# plug_in_A.net
KiCad netlist of a schematic drawn in EAGLE
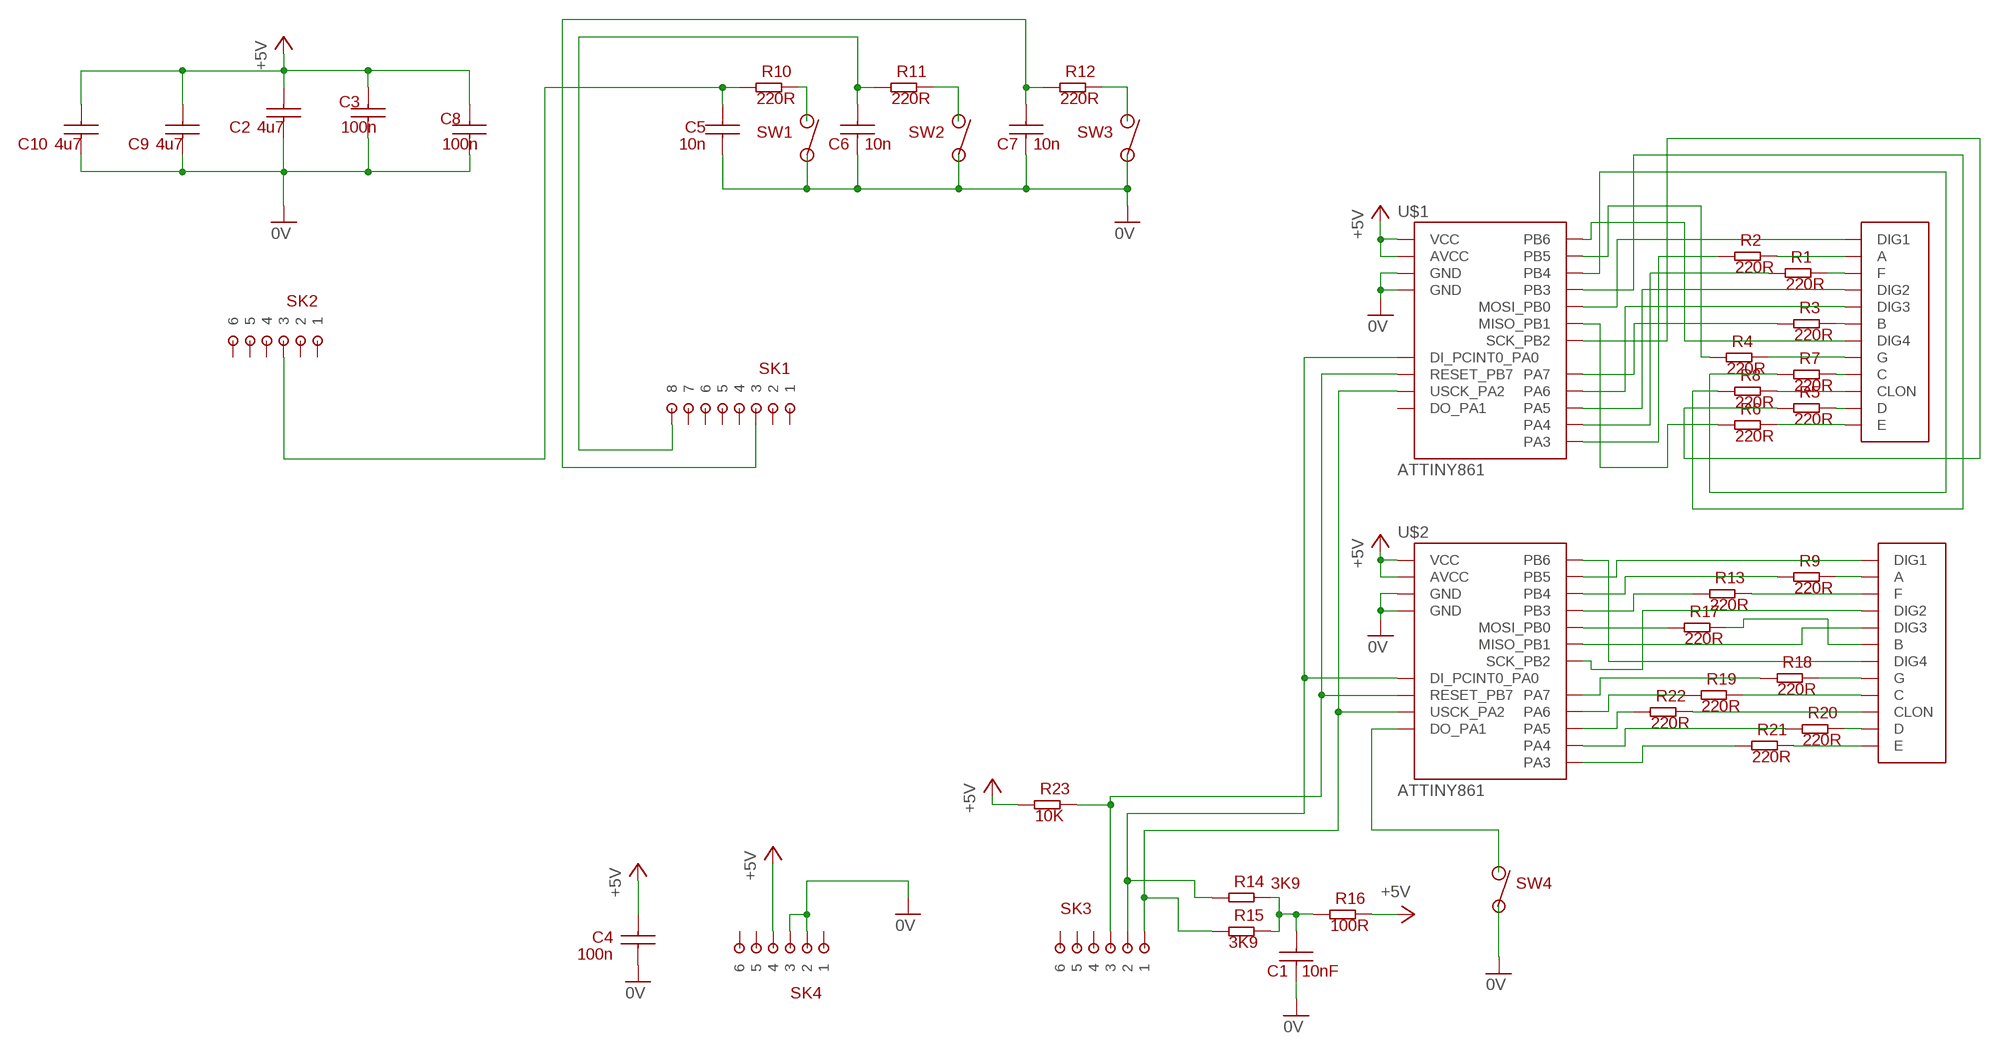
[diagram p0: schematic, sheet 1]

(export (version "E")
  (design (tool "Eeschema 10.0.6"))
  (components
    (comp (ref "C1")
      (value "10nF")
      (footprint "eagle-import:1206")
      (libsource (lib "eagle-import") (part "CAPACITOR"))
    )
    (comp (ref "C2")
      (value "4u7")
      (footprint "eagle-import:1206")
      (libsource (lib "eagle-import") (part "CAPACITOR"))
    )
    (comp (ref "C3")
      (value "100n")
      (footprint "eagle-import:1206")
      (libsource (lib "eagle-import") (part "CAPACITOR"))
    )
    (comp (ref "C4")
      (value "100n")
      (footprint "eagle-import:1206")
      (libsource (lib "eagle-import") (part "CAPACITOR"))
    )
    (comp (ref "C5")
      (value "10n")
      (footprint "eagle-import:1206")
      (libsource (lib "eagle-import") (part "CAPACITOR"))
    )
    (comp (ref "C6")
      (value "10n")
      (footprint "eagle-import:1206")
      (libsource (lib "eagle-import") (part "CAPACITOR"))
    )
    (comp (ref "C7")
      (value "10n")
      (footprint "eagle-import:1206")
      (libsource (lib "eagle-import") (part "CAPACITOR"))
    )
    (comp (ref "C8")
      (value "100n")
      (footprint "eagle-import:1206")
      (libsource (lib "eagle-import") (part "CAPACITOR"))
    )
    (comp (ref "C9")
      (value "4u7")
      (footprint "eagle-import:1206")
      (libsource (lib "eagle-import") (part "CAPACITOR"))
    )
    (comp (ref "C10")
      (value "4u7")
      (footprint "eagle-import:1206")
      (libsource (lib "eagle-import") (part "CAPACITOR"))
    )
    (comp (ref "R1")
      (value "220R")
      (footprint "eagle-import:1206")
      (libsource (lib "eagle-import") (part "RESISTOR"))
    )
    (comp (ref "R2")
      (value "220R")
      (footprint "eagle-import:1206")
      (libsource (lib "eagle-import") (part "RESISTOR"))
    )
    (comp (ref "R3")
      (value "220R")
      (footprint "eagle-import:1206")
      (libsource (lib "eagle-import") (part "RESISTOR"))
    )
    (comp (ref "R4")
      (value "220R")
      (footprint "eagle-import:1206")
      (libsource (lib "eagle-import") (part "RESISTOR"))
    )
    (comp (ref "R5")
      (value "220R")
      (footprint "eagle-import:1206")
      (libsource (lib "eagle-import") (part "RESISTOR"))
    )
    (comp (ref "R6")
      (value "220R")
      (footprint "eagle-import:1206")
      (libsource (lib "eagle-import") (part "RESISTOR"))
    )
    (comp (ref "R7")
      (value "220R")
      (footprint "eagle-import:1206")
      (libsource (lib "eagle-import") (part "RESISTOR"))
    )
    (comp (ref "R8")
      (value "220R")
      (footprint "eagle-import:1206")
      (libsource (lib "eagle-import") (part "RESISTOR"))
    )
    (comp (ref "R9")
      (value "220R")
      (footprint "eagle-import:1206")
      (libsource (lib "eagle-import") (part "RESISTOR"))
    )
    (comp (ref "R10")
      (value "220R")
      (footprint "eagle-import:1206")
      (libsource (lib "eagle-import") (part "RESISTOR"))
    )
    (comp (ref "R11")
      (value "220R")
      (footprint "eagle-import:1206")
      (libsource (lib "eagle-import") (part "RESISTOR"))
    )
    (comp (ref "R12")
      (value "220R")
      (footprint "eagle-import:1206")
      (libsource (lib "eagle-import") (part "RESISTOR"))
    )
    (comp (ref "R13")
      (value "220R")
      (footprint "eagle-import:1206")
      (libsource (lib "eagle-import") (part "RESISTOR"))
    )
    (comp (ref "R14")
      (value "3K9")
      (footprint "eagle-import:1206")
      (libsource (lib "eagle-import") (part "RESISTOR"))
    )
    (comp (ref "R15")
      (value "3K9")
      (footprint "eagle-import:1206")
      (libsource (lib "eagle-import") (part "RESISTOR"))
    )
    (comp (ref "R16")
      (value "100R")
      (footprint "eagle-import:1206")
      (libsource (lib "eagle-import") (part "RESISTOR"))
    )
    (comp (ref "R17")
      (value "220R")
      (footprint "eagle-import:1206")
      (libsource (lib "eagle-import") (part "RESISTOR"))
    )
    (comp (ref "R18")
      (value "220R")
      (footprint "eagle-import:1206")
      (libsource (lib "eagle-import") (part "RESISTOR"))
    )
    (comp (ref "R19")
      (value "220R")
      (footprint "eagle-import:1206")
      (libsource (lib "eagle-import") (part "RESISTOR"))
    )
    (comp (ref "R20")
      (value "220R")
      (footprint "eagle-import:1206")
      (libsource (lib "eagle-import") (part "RESISTOR"))
    )
    (comp (ref "R21")
      (value "220R")
      (footprint "eagle-import:1206")
      (libsource (lib "eagle-import") (part "RESISTOR"))
    )
    (comp (ref "R22")
      (value "220R")
      (footprint "eagle-import:1206")
      (libsource (lib "eagle-import") (part "RESISTOR"))
    )
    (comp (ref "R23")
      (value "10K")
      (footprint "eagle-import:1206")
      (libsource (lib "eagle-import") (part "RESISTOR"))
    )
    (comp (ref "SK1")
      (value "8_WAY_HEADER")
      (footprint "eagle-import:8_WAY_HEADER")
      (libsource (lib "eagle-import") (part "8_WAY_HEADER"))
    )
    (comp (ref "SK2")
      (value "6_WAY_HEADER")
      (footprint "eagle-import:6_WAY_HEADER")
      (libsource (lib "eagle-import") (part "6_WAY_HEADER"))
    )
    (comp (ref "SK3")
      (value "6_WAY_HEADER")
      (footprint "eagle-import:6_WAY_HEADER")
      (libsource (lib "eagle-import") (part "6_WAY_HEADER"))
    )
    (comp (ref "SK4")
      (value "6_WAY_HEADER")
      (footprint "eagle-import:6_WAY_HEADER")
      (libsource (lib "eagle-import") (part "6_WAY_HEADER"))
    )
    (comp (ref "SW1")
      (value "BP_TH_NO")
      (footprint "eagle-import:PB_NO_TH")
      (libsource (lib "eagle-import") (part "BP_TH_NO"))
    )
    (comp (ref "SW2")
      (value "BP_TH_NO")
      (footprint "eagle-import:PB_NO_TH")
      (libsource (lib "eagle-import") (part "BP_TH_NO"))
    )
    (comp (ref "SW3")
      (value "BP_TH_NO")
      (footprint "eagle-import:PB_NO_TH")
      (libsource (lib "eagle-import") (part "BP_TH_NO"))
    )
    (comp (ref "SW4")
      (value "PUSH_BUTTON_NO_SM")
      (footprint "eagle-import:PUSH_BUTTON_NO_SM")
      (libsource (lib "eagle-import") (part "PUSH_BUTTON_NO_SM"))
    )
    (comp (ref "U$1")
      (value "ATTINY861")
      (footprint "eagle-import:DIL20")
      (libsource (lib "eagle-import") (part "ATTINY861"))
    )
    (comp (ref "U$2")
      (value "ATTINY861")
      (footprint "eagle-import:DIL20")
      (libsource (lib "eagle-import") (part "ATTINY861"))
    )
    (comp (ref "U$3")
      (value "DISPLAY")
      (footprint "eagle-import:DISPLAY")
      (libsource (lib "eagle-import") (part "DISPLAY"))
    )
    (comp (ref "U$4")
      (value "DISPLAY")
      (footprint "eagle-import:DISPLAY")
      (libsource (lib "eagle-import") (part "DISPLAY"))
    )
  )
  (nets
    (net (code "1") (name "+5V") (class "Default")
      (node (ref "C10") (pin "P$2") (pinfunction "P$2_P$2") (pintype "bidirectional"))
      (node (ref "C2") (pin "P$2") (pinfunction "P$2_P$2") (pintype "bidirectional"))
      (node (ref "C3") (pin "P$2") (pinfunction "P$2_P$2") (pintype "bidirectional"))
      (node (ref "C4") (pin "P$2") (pinfunction "P$2_P$2") (pintype "bidirectional"))
      (node (ref "C8") (pin "P$2") (pinfunction "P$2_P$2") (pintype "bidirectional"))
      (node (ref "C9") (pin "P$2") (pinfunction "P$2_P$2") (pintype "bidirectional"))
      (node (ref "R16") (pin "P$2") (pinfunction "2_P$2") (pintype "bidirectional"))
      (node (ref "R23") (pin "P$1") (pinfunction "1_P$1") (pintype "bidirectional"))
      (node (ref "SK4") (pin "P$4") (pinfunction "4_P$4") (pintype "bidirectional"))
      (node (ref "U$1") (pin "15") (pinfunction "AVCC_15") (pintype "power_in"))
      (node (ref "U$1") (pin "5") (pinfunction "VCC_5") (pintype "power_in"))
      (node (ref "U$2") (pin "15") (pinfunction "AVCC_15") (pintype "power_in"))
      (node (ref "U$2") (pin "5") (pinfunction "VCC_5") (pintype "power_in"))
    )
    (net (code "2") (name "0V") (class "Default")
      (node (ref "C1") (pin "P$1") (pinfunction "P$1_P$1") (pintype "bidirectional"))
      (node (ref "C10") (pin "P$1") (pinfunction "P$1_P$1") (pintype "bidirectional"))
      (node (ref "C2") (pin "P$1") (pinfunction "P$1_P$1") (pintype "bidirectional"))
      (node (ref "C3") (pin "P$1") (pinfunction "P$1_P$1") (pintype "bidirectional"))
      (node (ref "C4") (pin "P$1") (pinfunction "P$1_P$1") (pintype "bidirectional"))
      (node (ref "C5") (pin "P$1") (pinfunction "P$1_P$1") (pintype "bidirectional"))
      (node (ref "C6") (pin "P$1") (pinfunction "P$1_P$1") (pintype "bidirectional"))
      (node (ref "C7") (pin "P$1") (pinfunction "P$1_P$1") (pintype "bidirectional"))
      (node (ref "C8") (pin "P$1") (pinfunction "P$1_P$1") (pintype "bidirectional"))
      (node (ref "C9") (pin "P$1") (pinfunction "P$1_P$1") (pintype "bidirectional"))
      (node (ref "SK4") (pin "P$2") (pinfunction "2_P$2") (pintype "bidirectional"))
      (node (ref "SK4") (pin "P$3") (pinfunction "3_P$3") (pintype "bidirectional"))
      (node (ref "SW1") (pin "P$2") (pinfunction "P$2_P$2") (pintype "bidirectional"))
      (node (ref "SW2") (pin "P$2") (pinfunction "P$2_P$2") (pintype "bidirectional"))
      (node (ref "SW3") (pin "P$2") (pinfunction "P$2_P$2") (pintype "bidirectional"))
      (node (ref "SW4") (pin "P$2") (pinfunction "P$2_P$2") (pintype "bidirectional"))
      (node (ref "U$1") (pin "16") (pinfunction "GND_16") (pintype "power_in"))
      (node (ref "U$1") (pin "6") (pinfunction "GND_6") (pintype "power_in"))
      (node (ref "U$2") (pin "16") (pinfunction "GND_16") (pintype "power_in"))
      (node (ref "U$2") (pin "6") (pinfunction "GND_6") (pintype "power_in"))
    )
    (net (code "3") (name "Net-(R1-1)") (class "Default")
      (node (ref "R1") (pin "P$1") (pinfunction "1_P$1") (pintype "bidirectional"))
      (node (ref "U$1") (pin "14") (pinfunction "PA4_14") (pintype "bidirectional"))
    )
    (net (code "4") (name "Net-(R1-2)") (class "Default")
      (node (ref "R1") (pin "P$2") (pinfunction "2_P$2") (pintype "bidirectional"))
      (node (ref "U$3") (pin "P$10") (pinfunction "F_P$10") (pintype "bidirectional"))
    )
    (net (code "5") (name "Net-(R2-1)") (class "Default")
      (node (ref "R2") (pin "P$1") (pinfunction "1_P$1") (pintype "bidirectional"))
      (node (ref "U$1") (pin "17") (pinfunction "PA3_17") (pintype "bidirectional"))
    )
    (net (code "6") (name "Net-(R2-2)") (class "Default")
      (node (ref "R2") (pin "P$2") (pinfunction "2_P$2") (pintype "bidirectional"))
      (node (ref "U$3") (pin "P$11") (pinfunction "A_P$11") (pintype "bidirectional"))
    )
    (net (code "7") (name "Net-(R3-1)") (class "Default")
      (node (ref "R3") (pin "P$1") (pinfunction "1_P$1") (pintype "bidirectional"))
      (node (ref "U$1") (pin "11") (pinfunction "PA7_11") (pintype "bidirectional"))
    )
    (net (code "8") (name "Net-(R3-2)") (class "Default")
      (node (ref "R3") (pin "P$2") (pinfunction "2_P$2") (pintype "bidirectional"))
      (node (ref "U$3") (pin "P$7") (pinfunction "B_P$7") (pintype "bidirectional"))
    )
    (net (code "9") (name "Net-(R4-1)") (class "Default")
      (node (ref "R4") (pin "P$1") (pinfunction "1_P$1") (pintype "bidirectional"))
      (node (ref "U$1") (pin "8") (pinfunction "PB5_8") (pintype "bidirectional"))
    )
    (net (code "10") (name "Net-(R4-2)") (class "Default")
      (node (ref "R4") (pin "P$2") (pinfunction "2_P$2") (pintype "bidirectional"))
      (node (ref "U$3") (pin "P$5") (pinfunction "G_P$5") (pintype "bidirectional"))
    )
    (net (code "11") (name "Net-(R5-1)") (class "Default")
      (node (ref "R5") (pin "P$1") (pinfunction "1_P$1") (pintype "bidirectional"))
      (node (ref "U$1") (pin "3") (pinfunction "SCK_PB2_3") (pintype "bidirectional"))
    )
    (net (code "12") (name "Net-(R5-2)") (class "Default")
      (node (ref "R5") (pin "P$2") (pinfunction "2_P$2") (pintype "bidirectional"))
      (node (ref "U$3") (pin "P$2") (pinfunction "D_P$2") (pintype "bidirectional"))
    )
    (net (code "13") (name "Net-(R6-1)") (class "Default")
      (node (ref "R6") (pin "P$1") (pinfunction "1_P$1") (pintype "bidirectional"))
      (node (ref "U$1") (pin "2") (pinfunction "MISO_PB1_2") (pintype "bidirectional"))
    )
    (net (code "14") (name "Net-(R6-2)") (class "Default")
      (node (ref "R6") (pin "P$2") (pinfunction "2_P$2") (pintype "bidirectional"))
      (node (ref "U$3") (pin "P$1") (pinfunction "E_P$1") (pintype "bidirectional"))
    )
    (net (code "15") (name "Net-(R7-1)") (class "Default")
      (node (ref "R7") (pin "P$1") (pinfunction "1_P$1") (pintype "bidirectional"))
      (node (ref "U$1") (pin "7") (pinfunction "PB4_7") (pintype "bidirectional"))
    )
    (net (code "16") (name "Net-(R7-2)") (class "Default")
      (node (ref "R7") (pin "P$2") (pinfunction "2_P$2") (pintype "bidirectional"))
      (node (ref "U$3") (pin "P$4") (pinfunction "C_P$4") (pintype "bidirectional"))
    )
    (net (code "17") (name "Net-(R8-1)") (class "Default")
      (node (ref "R8") (pin "P$1") (pinfunction "1_P$1") (pintype "bidirectional"))
      (node (ref "U$1") (pin "4") (pinfunction "PB3_4") (pintype "bidirectional"))
    )
    (net (code "18") (name "Net-(R8-2)") (class "Default")
      (node (ref "R8") (pin "P$2") (pinfunction "2_P$2") (pintype "bidirectional"))
      (node (ref "U$3") (pin "P$3") (pinfunction "CLON_P$3") (pintype "bidirectional"))
    )
    (net (code "19") (name "Net-(R9-1)") (class "Default")
      (node (ref "R9") (pin "P$1") (pinfunction "1_P$1") (pintype "bidirectional"))
      (node (ref "U$2") (pin "7") (pinfunction "PB4_7") (pintype "bidirectional"))
    )
    (net (code "20") (name "Net-(R9-2)") (class "Default")
      (node (ref "R9") (pin "P$2") (pinfunction "2_P$2") (pintype "bidirectional"))
      (node (ref "U$4") (pin "P$11") (pinfunction "A_P$11") (pintype "bidirectional"))
    )
    (net (code "21") (name "Net-(R10-1)") (class "Default")
      (node (ref "C5") (pin "P$2") (pinfunction "P$2_P$2") (pintype "bidirectional"))
      (node (ref "R10") (pin "P$1") (pinfunction "1_P$1") (pintype "bidirectional"))
      (node (ref "SK2") (pin "P$3") (pinfunction "3_P$3") (pintype "bidirectional"))
    )
    (net (code "22") (name "Net-(R10-2)") (class "Default")
      (node (ref "R10") (pin "P$2") (pinfunction "2_P$2") (pintype "bidirectional"))
      (node (ref "SW1") (pin "P$1") (pinfunction "P$1_P$1") (pintype "bidirectional"))
    )
    (net (code "23") (name "Net-(R11-1)") (class "Default")
      (node (ref "C6") (pin "P$2") (pinfunction "P$2_P$2") (pintype "bidirectional"))
      (node (ref "R11") (pin "P$1") (pinfunction "1_P$1") (pintype "bidirectional"))
      (node (ref "SK1") (pin "P$8") (pinfunction "8_P$8") (pintype "bidirectional"))
    )
    (net (code "24") (name "Net-(R11-2)") (class "Default")
      (node (ref "R11") (pin "P$2") (pinfunction "2_P$2") (pintype "bidirectional"))
      (node (ref "SW2") (pin "P$1") (pinfunction "P$1_P$1") (pintype "bidirectional"))
    )
    (net (code "25") (name "Net-(R12-1)") (class "Default")
      (node (ref "C7") (pin "P$2") (pinfunction "P$2_P$2") (pintype "bidirectional"))
      (node (ref "R12") (pin "P$1") (pinfunction "1_P$1") (pintype "bidirectional"))
      (node (ref "SK1") (pin "P$3") (pinfunction "3_P$3") (pintype "bidirectional"))
    )
    (net (code "26") (name "Net-(R12-2)") (class "Default")
      (node (ref "R12") (pin "P$2") (pinfunction "2_P$2") (pintype "bidirectional"))
      (node (ref "SW3") (pin "P$1") (pinfunction "P$1_P$1") (pintype "bidirectional"))
    )
    (net (code "27") (name "Net-(R13-1)") (class "Default")
      (node (ref "R13") (pin "P$1") (pinfunction "1_P$1") (pintype "bidirectional"))
      (node (ref "U$2") (pin "4") (pinfunction "PB3_4") (pintype "bidirectional"))
    )
    (net (code "28") (name "Net-(R13-2)") (class "Default")
      (node (ref "R13") (pin "P$2") (pinfunction "2_P$2") (pintype "bidirectional"))
      (node (ref "U$4") (pin "P$10") (pinfunction "F_P$10") (pintype "bidirectional"))
    )
    (net (code "29") (name "Net-(R14-1)") (class "Default")
      (node (ref "R14") (pin "P$1") (pinfunction "1_P$1") (pintype "bidirectional"))
      (node (ref "SK3") (pin "P$2") (pinfunction "2_P$2") (pintype "bidirectional"))
      (node (ref "U$1") (pin "20") (pinfunction "DI_PCINT0_PA0_20") (pintype "bidirectional"))
      (node (ref "U$2") (pin "20") (pinfunction "DI_PCINT0_PA0_20") (pintype "bidirectional"))
    )
    (net (code "30") (name "Net-(R14-2)") (class "Default")
      (node (ref "C1") (pin "P$2") (pinfunction "P$2_P$2") (pintype "bidirectional"))
      (node (ref "R14") (pin "P$2") (pinfunction "2_P$2") (pintype "bidirectional"))
      (node (ref "R15") (pin "P$2") (pinfunction "2_P$2") (pintype "bidirectional"))
      (node (ref "R16") (pin "P$1") (pinfunction "1_P$1") (pintype "bidirectional"))
    )
    (net (code "31") (name "Net-(R15-1)") (class "Default")
      (node (ref "R15") (pin "P$1") (pinfunction "1_P$1") (pintype "bidirectional"))
      (node (ref "SK3") (pin "P$1") (pinfunction "1_P$1") (pintype "bidirectional"))
      (node (ref "U$1") (pin "18") (pinfunction "USCK_PA2_18") (pintype "bidirectional"))
      (node (ref "U$2") (pin "18") (pinfunction "USCK_PA2_18") (pintype "bidirectional"))
    )
    (net (code "32") (name "Net-(R17-1)") (class "Default")
      (node (ref "R17") (pin "P$1") (pinfunction "1_P$1") (pintype "bidirectional"))
      (node (ref "U$2") (pin "1") (pinfunction "MOSI_PB0_1") (pintype "bidirectional"))
    )
    (net (code "33") (name "Net-(R17-2)") (class "Default")
      (node (ref "R17") (pin "P$2") (pinfunction "2_P$2") (pintype "bidirectional"))
      (node (ref "U$4") (pin "P$7") (pinfunction "B_P$7") (pintype "bidirectional"))
    )
    (net (code "34") (name "Net-(R18-1)") (class "Default")
      (node (ref "R18") (pin "P$1") (pinfunction "1_P$1") (pintype "bidirectional"))
      (node (ref "U$2") (pin "11") (pinfunction "PA7_11") (pintype "bidirectional"))
    )
    (net (code "35") (name "Net-(R18-2)") (class "Default")
      (node (ref "R18") (pin "P$2") (pinfunction "2_P$2") (pintype "bidirectional"))
      (node (ref "U$4") (pin "P$5") (pinfunction "G_P$5") (pintype "bidirectional"))
    )
    (net (code "36") (name "Net-(R19-1)") (class "Default")
      (node (ref "R19") (pin "P$1") (pinfunction "1_P$1") (pintype "bidirectional"))
      (node (ref "U$2") (pin "12") (pinfunction "PA6_12") (pintype "bidirectional"))
    )
    (net (code "37") (name "Net-(R19-2)") (class "Default")
      (node (ref "R19") (pin "P$2") (pinfunction "2_P$2") (pintype "bidirectional"))
      (node (ref "U$4") (pin "P$4") (pinfunction "C_P$4") (pintype "bidirectional"))
    )
    (net (code "38") (name "Net-(R20-1)") (class "Default")
      (node (ref "R20") (pin "P$1") (pinfunction "1_P$1") (pintype "bidirectional"))
      (node (ref "U$2") (pin "14") (pinfunction "PA4_14") (pintype "bidirectional"))
    )
    (net (code "39") (name "Net-(R20-2)") (class "Default")
      (node (ref "R20") (pin "P$2") (pinfunction "2_P$2") (pintype "bidirectional"))
      (node (ref "U$4") (pin "P$2") (pinfunction "D_P$2") (pintype "bidirectional"))
    )
    (net (code "40") (name "Net-(R21-1)") (class "Default")
      (node (ref "R21") (pin "P$1") (pinfunction "1_P$1") (pintype "bidirectional"))
      (node (ref "U$2") (pin "17") (pinfunction "PA3_17") (pintype "bidirectional"))
    )
    (net (code "41") (name "Net-(R21-2)") (class "Default")
      (node (ref "R21") (pin "P$2") (pinfunction "2_P$2") (pintype "bidirectional"))
      (node (ref "U$4") (pin "P$1") (pinfunction "E_P$1") (pintype "bidirectional"))
    )
    (net (code "42") (name "Net-(R22-1)") (class "Default")
      (node (ref "R22") (pin "P$1") (pinfunction "1_P$1") (pintype "bidirectional"))
      (node (ref "U$2") (pin "13") (pinfunction "PA5_13") (pintype "bidirectional"))
    )
    (net (code "43") (name "Net-(R22-2)") (class "Default")
      (node (ref "R22") (pin "P$2") (pinfunction "2_P$2") (pintype "bidirectional"))
      (node (ref "U$4") (pin "P$3") (pinfunction "CLON_P$3") (pintype "bidirectional"))
    )
    (net (code "44") (name "Net-(R23-2)") (class "Default")
      (node (ref "R23") (pin "P$2") (pinfunction "2_P$2") (pintype "bidirectional"))
      (node (ref "SK3") (pin "P$3") (pinfunction "3_P$3") (pintype "bidirectional"))
      (node (ref "U$1") (pin "10") (pinfunction "RESET_PB7_10") (pintype "bidirectional"))
      (node (ref "U$2") (pin "10") (pinfunction "RESET_PB7_10") (pintype "bidirectional"))
    )
    (net (code "45") (name "Net-(U$1-MOSI_PB0)") (class "Default")
      (node (ref "U$1") (pin "1") (pinfunction "MOSI_PB0_1") (pintype "bidirectional"))
      (node (ref "U$3") (pin "P$12") (pinfunction "DIG1_P$12") (pintype "bidirectional"))
    )
    (net (code "46") (name "Net-(U$1-PA5)") (class "Default")
      (node (ref "U$1") (pin "13") (pinfunction "PA5_13") (pintype "bidirectional"))
      (node (ref "U$3") (pin "P$9") (pinfunction "DIG2_P$9") (pintype "bidirectional"))
    )
    (net (code "47") (name "Net-(U$1-PA6)") (class "Default")
      (node (ref "U$1") (pin "12") (pinfunction "PA6_12") (pintype "bidirectional"))
      (node (ref "U$3") (pin "P$8") (pinfunction "DIG3_P$8") (pintype "bidirectional"))
    )
    (net (code "48") (name "Net-(U$1-PB6)") (class "Default")
      (node (ref "U$1") (pin "9") (pinfunction "PB6_9") (pintype "bidirectional"))
      (node (ref "U$3") (pin "P$6") (pinfunction "DIG4_P$6") (pintype "bidirectional"))
    )
    (net (code "49") (name "Net-(U$2-DO_PA1)") (class "Default")
      (node (ref "SW4") (pin "P$1") (pinfunction "P$1_P$1") (pintype "bidirectional"))
      (node (ref "U$2") (pin "19") (pinfunction "DO_PA1_19") (pintype "bidirectional"))
    )
    (net (code "50") (name "Net-(U$2-MISO_PB1)") (class "Default")
      (node (ref "U$2") (pin "2") (pinfunction "MISO_PB1_2") (pintype "bidirectional"))
      (node (ref "U$4") (pin "P$8") (pinfunction "DIG3_P$8") (pintype "bidirectional"))
    )
    (net (code "51") (name "Net-(U$2-PB5)") (class "Default")
      (node (ref "U$2") (pin "8") (pinfunction "PB5_8") (pintype "bidirectional"))
      (node (ref "U$4") (pin "P$12") (pinfunction "DIG1_P$12") (pintype "bidirectional"))
    )
    (net (code "52") (name "Net-(U$2-PB6)") (class "Default")
      (node (ref "U$2") (pin "9") (pinfunction "PB6_9") (pintype "bidirectional"))
      (node (ref "U$4") (pin "P$6") (pinfunction "DIG4_P$6") (pintype "bidirectional"))
    )
    (net (code "53") (name "Net-(U$2-SCK_PB2)") (class "Default")
      (node (ref "U$2") (pin "3") (pinfunction "SCK_PB2_3") (pintype "bidirectional"))
      (node (ref "U$4") (pin "P$9") (pinfunction "DIG2_P$9") (pintype "bidirectional"))
    )
    (net (code "54") (name "unconnected-(SK1-1-PadP$1)") (class "Default")
      (node (ref "SK1") (pin "P$1") (pinfunction "1_P$1") (pintype "bidirectional"))
    )
    (net (code "55") (name "unconnected-(SK1-2-PadP$2)") (class "Default")
      (node (ref "SK1") (pin "P$2") (pinfunction "2_P$2") (pintype "bidirectional"))
    )
    (net (code "56") (name "unconnected-(SK1-4-PadP$4)") (class "Default")
      (node (ref "SK1") (pin "P$4") (pinfunction "4_P$4") (pintype "bidirectional"))
    )
    (net (code "57") (name "unconnected-(SK1-5-PadP$5)") (class "Default")
      (node (ref "SK1") (pin "P$5") (pinfunction "5_P$5") (pintype "bidirectional"))
    )
    (net (code "58") (name "unconnected-(SK1-6-PadP$6)") (class "Default")
      (node (ref "SK1") (pin "P$6") (pinfunction "6_P$6") (pintype "bidirectional"))
    )
    (net (code "59") (name "unconnected-(SK1-7-PadP$7)") (class "Default")
      (node (ref "SK1") (pin "P$7") (pinfunction "7_P$7") (pintype "bidirectional"))
    )
    (net (code "60") (name "unconnected-(SK2-1-PadP$1)") (class "Default")
      (node (ref "SK2") (pin "P$1") (pinfunction "1_P$1") (pintype "bidirectional"))
    )
    (net (code "61") (name "unconnected-(SK2-2-PadP$2)") (class "Default")
      (node (ref "SK2") (pin "P$2") (pinfunction "2_P$2") (pintype "bidirectional"))
    )
    (net (code "62") (name "unconnected-(SK2-4-PadP$4)") (class "Default")
      (node (ref "SK2") (pin "P$4") (pinfunction "4_P$4") (pintype "bidirectional"))
    )
    (net (code "63") (name "unconnected-(SK2-5-PadP$5)") (class "Default")
      (node (ref "SK2") (pin "P$5") (pinfunction "5_P$5") (pintype "bidirectional"))
    )
    (net (code "64") (name "unconnected-(SK2-6-PadP$6)") (class "Default")
      (node (ref "SK2") (pin "P$6") (pinfunction "6_P$6") (pintype "bidirectional"))
    )
    (net (code "65") (name "unconnected-(SK3-4-PadP$4)") (class "Default")
      (node (ref "SK3") (pin "P$4") (pinfunction "4_P$4") (pintype "bidirectional"))
    )
    (net (code "66") (name "unconnected-(SK3-5-PadP$5)") (class "Default")
      (node (ref "SK3") (pin "P$5") (pinfunction "5_P$5") (pintype "bidirectional"))
    )
    (net (code "67") (name "unconnected-(SK3-6-PadP$6)") (class "Default")
      (node (ref "SK3") (pin "P$6") (pinfunction "6_P$6") (pintype "bidirectional"))
    )
    (net (code "68") (name "unconnected-(SK4-1-PadP$1)") (class "Default")
      (node (ref "SK4") (pin "P$1") (pinfunction "1_P$1") (pintype "bidirectional"))
    )
    (net (code "69") (name "unconnected-(SK4-5-PadP$5)") (class "Default")
      (node (ref "SK4") (pin "P$5") (pinfunction "5_P$5") (pintype "bidirectional"))
    )
    (net (code "70") (name "unconnected-(SK4-6-PadP$6)") (class "Default")
      (node (ref "SK4") (pin "P$6") (pinfunction "6_P$6") (pintype "bidirectional"))
    )
    (net (code "71") (name "unconnected-(U$1-DO_PA1-Pad19)") (class "Default")
      (node (ref "U$1") (pin "19") (pinfunction "DO_PA1_19") (pintype "bidirectional"))
    )
  )
)
